# 3_PowerDistribution.net
KiCad netlist of a schematic drawn in Altium Designer
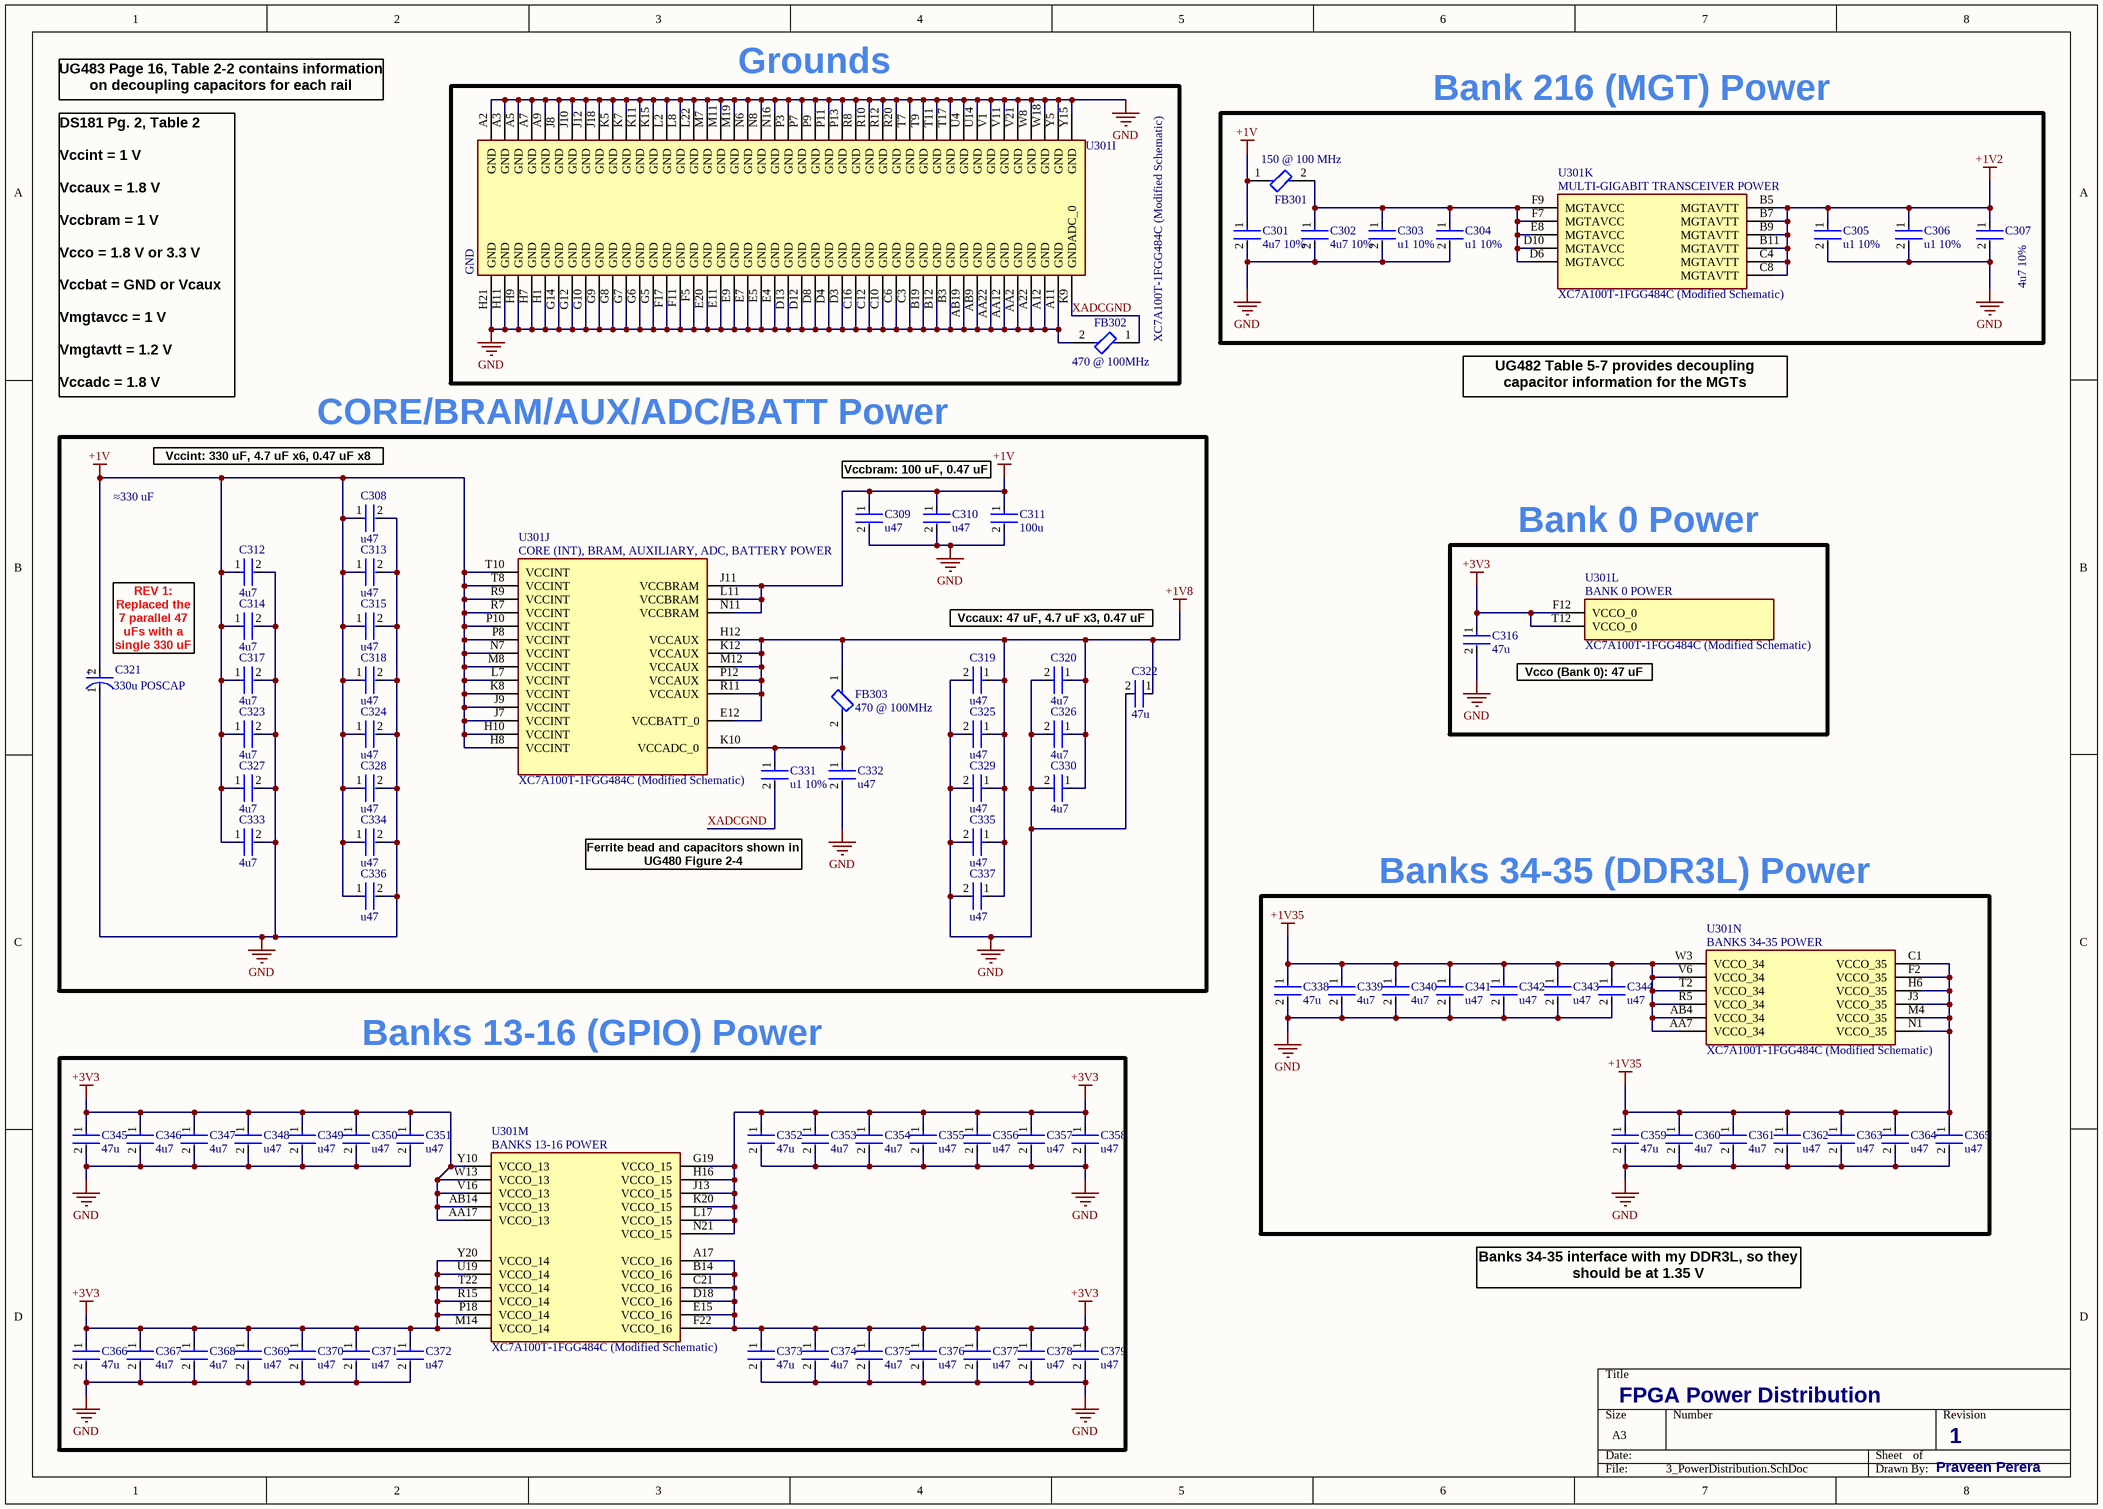
[diagram p0: 3_PowerDistribution.SchDoc]

(export (version "E")
  (design (tool "Eeschema 10.0.6"))
  (components
    (comp (ref "C301")
      (value "4u7 10%")
      (footprint "FP-C1005-050-0_20-0_10-MFG")
      (description "C1005X5R1A475K050BE\r\n\r\nCAP CER 4.7UF 10V X5R 0402")
      (fields (field (name "TOLERANCE") "10%"))
      (libsource (lib "Altium Content Vault") (part "b4654b650e69147ec39a6b967a45e02"))
    )
    (comp (ref "C302")
      (value "4u7 10%")
      (footprint "FP-C1005-050-0_20-0_10-MFG")
      (description "C1005X5R1A475K050BE\r\n\r\nCAP CER 4.7UF 10V X5R 0402")
      (fields (field (name "TOLERANCE") "10%"))
      (libsource (lib "Altium Content Vault") (part "b4654b650e69147ec39a6b967a45e02"))
    )
    (comp (ref "C303")
      (value "u1 10%")
      (footprint "FP-CL891-IPC_C")
      (description "CL05B104KB5NNNC\r\n\r\nCap Ceramic 100nF 50V X7R ±10% SMD 0402 +125°C Paper T/R")
      (libsource (lib "Altium Content Vault") (part "b4654b650e69147ec39a6b967a45e02"))
    )
    (comp (ref "C304")
      (value "u1 10%")
      (footprint "FP-CL891-IPC_C")
      (description "CL05B104KB5NNNC\r\n\r\nCap Ceramic 100nF 50V X7R ±10% SMD 0402 +125°C Paper T/R")
      (libsource (lib "Altium Content Vault") (part "b4654b650e69147ec39a6b967a45e02"))
    )
    (comp (ref "C305")
      (value "u1 10%")
      (footprint "FP-CL891-IPC_C")
      (description "CL05B104KB5NNNC\r\n\r\nCap Ceramic 100nF 50V X7R ±10% SMD 0402 +125°C Paper T/R")
      (libsource (lib "Altium Content Vault") (part "b4654b650e69147ec39a6b967a45e02"))
    )
    (comp (ref "C306")
      (value "u1 10%")
      (footprint "FP-CL891-IPC_C")
      (description "CL05B104KB5NNNC\r\n\r\nCap Ceramic 100nF 50V X7R ±10% SMD 0402 +125°C Paper T/R")
      (libsource (lib "Altium Content Vault") (part "b4654b650e69147ec39a6b967a45e02"))
    )
    (comp (ref "C307")
      (value "4u7 10%")
      (footprint "FP-C1005-050-0_20-0_10-MFG")
      (description "C1005X5R1A475K050BE\r\n\r\nCAP CER 4.7UF 10V X5R 0402")
      (fields (field (name "TOLERANCE") "10%"))
      (libsource (lib "Altium Content Vault") (part "b4654b650e69147ec39a6b967a45e02"))
    )
    (comp (ref "C308")
      (value "u47")
      (footprint "FP-C0603-030-0_03-IPC_A")
      (description "C0603X5R1A474M030BC\r\n\r\nMultilayer Ceramic Capacitors 470nF ±20% 10V X5R SMD 0201")
      (fields (field (name "TOLERANCE") "20%"))
      (libsource (lib "Altium Content Vault") (part "02cd4be3c70576c341d710602a673aa"))
    )
    (comp (ref "C309")
      (value "u47")
      (footprint "FP-C0603-030-0_03-IPC_A")
      (description "C0603X5R1A474M030BC\r\n\r\nMultilayer Ceramic Capacitors 470nF ±20% 10V X5R SMD 0201")
      (fields (field (name "TOLERANCE") "20%"))
      (libsource (lib "Altium Content Vault") (part "02cd4be3c70576c341d710602a673aa"))
    )
    (comp (ref "C310")
      (value "u47")
      (footprint "FP-C0603-030-0_03-IPC_A")
      (description "C0603X5R1A474M030BC\r\n\r\nMultilayer Ceramic Capacitors 470nF ±20% 10V X5R SMD 0201")
      (fields (field (name "TOLERANCE") "20%"))
      (libsource (lib "Altium Content Vault") (part "02cd4be3c70576c341d710602a673aa"))
    )
    (comp (ref "C311")
      (value "100u")
      (footprint "FP-GRM21B-0_2-e0_2_0_7-IPC_A")
      (fields (field (name "TOLERANCE") "20%"))
      (libsource (lib "Altium Content Vault") (part "b4654b650e69147ec39a6b967a45e02"))
    )
    (comp (ref "C312")
      (value "4u7")
      (footprint "FP-CL829-IPC_C")
      (description "CL05A475MO5NUNC\r\n\r\nCap Ceramic 4.7uF 16V X5R ±20% SMD 0402 +85°C Paper T/R")
      (fields (field (name "TOLERANCE") "20%"))
      (libsource (lib "Altium Content Vault") (part "b4654b650e69147ec39a6b967a45e02"))
    )
    (comp (ref "C313")
      (value "u47")
      (footprint "FP-C0603-030-0_03-IPC_A")
      (description "C0603X5R1A474M030BC\r\n\r\nMultilayer Ceramic Capacitors 470nF ±20% 10V X5R SMD 0201")
      (fields (field (name "TOLERANCE") "20%"))
      (libsource (lib "Altium Content Vault") (part "02cd4be3c70576c341d710602a673aa"))
    )
    (comp (ref "C314")
      (value "4u7")
      (footprint "FP-CL829-IPC_C")
      (description "CL05A475MO5NUNC\r\n\r\nCap Ceramic 4.7uF 16V X5R ±20% SMD 0402 +85°C Paper T/R")
      (fields (field (name "TOLERANCE") "20%"))
      (libsource (lib "Altium Content Vault") (part "b4654b650e69147ec39a6b967a45e02"))
    )
    (comp (ref "C315")
      (value "u47")
      (footprint "FP-C0603-030-0_03-IPC_A")
      (description "C0603X5R1A474M030BC\r\n\r\nMultilayer Ceramic Capacitors 470nF ±20% 10V X5R SMD 0201")
      (fields (field (name "TOLERANCE") "20%"))
      (libsource (lib "Altium Content Vault") (part "02cd4be3c70576c341d710602a673aa"))
    )
    (comp (ref "C316")
      (value "47u")
      (footprint "FP-GRM188-0_2-IPC_B")
      (fields (field (name "TOLERANCE") "20%"))
      (libsource (lib "Altium Content Vault") (part "11868f565c42a9108669ba33697ecf6"))
    )
    (comp (ref "C317")
      (value "4u7")
      (footprint "FP-CL829-IPC_C")
      (description "CL05A475MO5NUNC\r\n\r\nCap Ceramic 4.7uF 16V X5R ±20% SMD 0402 +85°C Paper T/R")
      (fields (field (name "TOLERANCE") "20%"))
      (libsource (lib "Altium Content Vault") (part "b4654b650e69147ec39a6b967a45e02"))
    )
    (comp (ref "C318")
      (value "u47")
      (footprint "FP-C0603-030-0_03-IPC_A")
      (description "C0603X5R1A474M030BC\r\n\r\nMultilayer Ceramic Capacitors 470nF ±20% 10V X5R SMD 0201")
      (fields (field (name "TOLERANCE") "20%"))
      (libsource (lib "Altium Content Vault") (part "02cd4be3c70576c341d710602a673aa"))
    )
    (comp (ref "C319")
      (value "u47")
      (footprint "FP-C0603-030-0_03-IPC_A")
      (description "C0603X5R1A474M030BC\r\n\r\nMultilayer Ceramic Capacitors 470nF ±20% 10V X5R SMD 0201")
      (fields (field (name "TOLERANCE") "20%"))
      (libsource (lib "Altium Content Vault") (part "02cd4be3c70576c341d710602a673aa"))
    )
    (comp (ref "C320")
      (value "4u7")
      (footprint "FP-CL829-IPC_C")
      (description "CL05A475MO5NUNC\r\n\r\nCap Ceramic 4.7uF 16V X5R ±20% SMD 0402 +85°C Paper T/R")
      (fields (field (name "TOLERANCE") "20%"))
      (libsource (lib "Altium Content Vault") (part "b4654b650e69147ec39a6b967a45e02"))
    )
    (comp (ref "C321")
      (value "330u POSCAP")
      (footprint "FP-POSCAP-D4-MFG")
      (description "10TCE330M\r\n\r\nCAP TANT POLY 330UF 10V 2917")
      (fields (field (name "TOLERANCE") "20%"))
      (libsource (lib "Altium Content Vault") (part "203bc49f2ac43e59fd269a8c329ed05"))
    )
    (comp (ref "C322")
      (value "47u")
      (footprint "FP-GRM188-0_2-IPC_B")
      (fields (field (name "TOLERANCE") "20%"))
      (libsource (lib "Altium Content Vault") (part "11868f565c42a9108669ba33697ecf6"))
    )
    (comp (ref "C323")
      (value "4u7")
      (footprint "FP-CL829-IPC_C")
      (description "CL05A475MO5NUNC\r\n\r\nCap Ceramic 4.7uF 16V X5R ±20% SMD 0402 +85°C Paper T/R")
      (fields (field (name "TOLERANCE") "20%"))
      (libsource (lib "Altium Content Vault") (part "b4654b650e69147ec39a6b967a45e02"))
    )
    (comp (ref "C324")
      (value "u47")
      (footprint "FP-C0603-030-0_03-IPC_A")
      (description "C0603X5R1A474M030BC\r\n\r\nMultilayer Ceramic Capacitors 470nF ±20% 10V X5R SMD 0201")
      (fields (field (name "TOLERANCE") "20%"))
      (libsource (lib "Altium Content Vault") (part "02cd4be3c70576c341d710602a673aa"))
    )
    (comp (ref "C325")
      (value "u47")
      (footprint "FP-C0603-030-0_03-IPC_A")
      (description "C0603X5R1A474M030BC\r\n\r\nMultilayer Ceramic Capacitors 470nF ±20% 10V X5R SMD 0201")
      (fields (field (name "TOLERANCE") "20%"))
      (libsource (lib "Altium Content Vault") (part "02cd4be3c70576c341d710602a673aa"))
    )
    (comp (ref "C326")
      (value "4u7")
      (footprint "FP-CL829-IPC_C")
      (description "CL05A475MO5NUNC\r\n\r\nCap Ceramic 4.7uF 16V X5R ±20% SMD 0402 +85°C Paper T/R")
      (fields (field (name "TOLERANCE") "20%"))
      (libsource (lib "Altium Content Vault") (part "b4654b650e69147ec39a6b967a45e02"))
    )
    (comp (ref "C327")
      (value "4u7")
      (footprint "FP-CL829-IPC_C")
      (description "CL05A475MO5NUNC\r\n\r\nCap Ceramic 4.7uF 16V X5R ±20% SMD 0402 +85°C Paper T/R")
      (fields (field (name "TOLERANCE") "20%"))
      (libsource (lib "Altium Content Vault") (part "b4654b650e69147ec39a6b967a45e02"))
    )
    (comp (ref "C328")
      (value "u47")
      (footprint "FP-C0603-030-0_03-IPC_A")
      (description "C0603X5R1A474M030BC\r\n\r\nMultilayer Ceramic Capacitors 470nF ±20% 10V X5R SMD 0201")
      (fields (field (name "TOLERANCE") "20%"))
      (libsource (lib "Altium Content Vault") (part "02cd4be3c70576c341d710602a673aa"))
    )
    (comp (ref "C329")
      (value "u47")
      (footprint "FP-C0603-030-0_03-IPC_A")
      (description "C0603X5R1A474M030BC\r\n\r\nMultilayer Ceramic Capacitors 470nF ±20% 10V X5R SMD 0201")
      (fields (field (name "TOLERANCE") "20%"))
      (libsource (lib "Altium Content Vault") (part "02cd4be3c70576c341d710602a673aa"))
    )
    (comp (ref "C330")
      (value "4u7")
      (footprint "FP-CL829-IPC_C")
      (description "CL05A475MO5NUNC\r\n\r\nCap Ceramic 4.7uF 16V X5R ±20% SMD 0402 +85°C Paper T/R")
      (fields (field (name "TOLERANCE") "20%"))
      (libsource (lib "Altium Content Vault") (part "b4654b650e69147ec39a6b967a45e02"))
    )
    (comp (ref "C331")
      (value "u1 10%")
      (footprint "FP-CL891-IPC_C")
      (description "CL05B104KB5NNNC\r\n\r\nCap Ceramic 100nF 50V X7R ±10% SMD 0402 +125°C Paper T/R")
      (libsource (lib "Altium Content Vault") (part "b4654b650e69147ec39a6b967a45e02"))
    )
    (comp (ref "C332")
      (value "u47")
      (footprint "FP-C0603-030-0_03-IPC_A")
      (description "C0603X5R1A474M030BC\r\n\r\nMultilayer Ceramic Capacitors 470nF ±20% 10V X5R SMD 0201")
      (fields (field (name "TOLERANCE") "20%"))
      (libsource (lib "Altium Content Vault") (part "02cd4be3c70576c341d710602a673aa"))
    )
    (comp (ref "C333")
      (value "4u7")
      (footprint "FP-CL829-IPC_C")
      (description "CL05A475MO5NUNC\r\n\r\nCap Ceramic 4.7uF 16V X5R ±20% SMD 0402 +85°C Paper T/R")
      (fields (field (name "TOLERANCE") "20%"))
      (libsource (lib "Altium Content Vault") (part "b4654b650e69147ec39a6b967a45e02"))
    )
    (comp (ref "C334")
      (value "u47")
      (footprint "FP-C0603-030-0_03-IPC_A")
      (description "C0603X5R1A474M030BC\r\n\r\nMultilayer Ceramic Capacitors 470nF ±20% 10V X5R SMD 0201")
      (fields (field (name "TOLERANCE") "20%"))
      (libsource (lib "Altium Content Vault") (part "02cd4be3c70576c341d710602a673aa"))
    )
    (comp (ref "C335")
      (value "u47")
      (footprint "FP-C0603-030-0_03-IPC_A")
      (description "C0603X5R1A474M030BC\r\n\r\nMultilayer Ceramic Capacitors 470nF ±20% 10V X5R SMD 0201")
      (fields (field (name "TOLERANCE") "20%"))
      (libsource (lib "Altium Content Vault") (part "02cd4be3c70576c341d710602a673aa"))
    )
    (comp (ref "C336")
      (value "u47")
      (footprint "FP-C0603-030-0_03-IPC_A")
      (description "C0603X5R1A474M030BC\r\n\r\nMultilayer Ceramic Capacitors 470nF ±20% 10V X5R SMD 0201")
      (fields (field (name "TOLERANCE") "20%"))
      (libsource (lib "Altium Content Vault") (part "02cd4be3c70576c341d710602a673aa"))
    )
    (comp (ref "C337")
      (value "u47")
      (footprint "FP-C0603-030-0_03-IPC_A")
      (description "C0603X5R1A474M030BC\r\n\r\nMultilayer Ceramic Capacitors 470nF ±20% 10V X5R SMD 0201")
      (fields (field (name "TOLERANCE") "20%"))
      (libsource (lib "Altium Content Vault") (part "02cd4be3c70576c341d710602a673aa"))
    )
    (comp (ref "C338")
      (value "47u")
      (footprint "FP-GRM188-0_2-IPC_B")
      (fields (field (name "TOLERANCE") "20%"))
      (libsource (lib "Altium Content Vault") (part "11868f565c42a9108669ba33697ecf6"))
    )
    (comp (ref "C339")
      (value "4u7")
      (footprint "FP-CL829-IPC_C")
      (description "CL05A475MO5NUNC\r\n\r\nCap Ceramic 4.7uF 16V X5R ±20% SMD 0402 +85°C Paper T/R")
      (fields (field (name "TOLERANCE") "20%"))
      (libsource (lib "Altium Content Vault") (part "b4654b650e69147ec39a6b967a45e02"))
    )
    (comp (ref "C340")
      (value "4u7")
      (footprint "FP-CL829-IPC_C")
      (description "CL05A475MO5NUNC\r\n\r\nCap Ceramic 4.7uF 16V X5R ±20% SMD 0402 +85°C Paper T/R")
      (fields (field (name "TOLERANCE") "20%"))
      (libsource (lib "Altium Content Vault") (part "b4654b650e69147ec39a6b967a45e02"))
    )
    (comp (ref "C341")
      (value "u47")
      (footprint "FP-C0603-030-0_03-IPC_A")
      (description "C0603X5R1A474M030BC\r\n\r\nMultilayer Ceramic Capacitors 470nF ±20% 10V X5R SMD 0201")
      (fields (field (name "TOLERANCE") "20%"))
      (libsource (lib "Altium Content Vault") (part "02cd4be3c70576c341d710602a673aa"))
    )
    (comp (ref "C342")
      (value "u47")
      (footprint "FP-C0603-030-0_03-IPC_A")
      (description "C0603X5R1A474M030BC\r\n\r\nMultilayer Ceramic Capacitors 470nF ±20% 10V X5R SMD 0201")
      (fields (field (name "TOLERANCE") "20%"))
      (libsource (lib "Altium Content Vault") (part "02cd4be3c70576c341d710602a673aa"))
    )
    (comp (ref "C343")
      (value "u47")
      (footprint "FP-C0603-030-0_03-IPC_A")
      (description "C0603X5R1A474M030BC\r\n\r\nMultilayer Ceramic Capacitors 470nF ±20% 10V X5R SMD 0201")
      (fields (field (name "TOLERANCE") "20%"))
      (libsource (lib "Altium Content Vault") (part "02cd4be3c70576c341d710602a673aa"))
    )
    (comp (ref "C344")
      (value "u47")
      (footprint "FP-C0603-030-0_03-IPC_A")
      (description "C0603X5R1A474M030BC\r\n\r\nMultilayer Ceramic Capacitors 470nF ±20% 10V X5R SMD 0201")
      (fields (field (name "TOLERANCE") "20%"))
      (libsource (lib "Altium Content Vault") (part "02cd4be3c70576c341d710602a673aa"))
    )
    (comp (ref "C345")
      (value "47u")
      (footprint "FP-GRM188-0_2-IPC_B")
      (fields (field (name "TOLERANCE") "20%"))
      (libsource (lib "Altium Content Vault") (part "11868f565c42a9108669ba33697ecf6"))
    )
    (comp (ref "C346")
      (value "4u7")
      (footprint "FP-CL829-IPC_C")
      (description "CL05A475MO5NUNC\r\n\r\nCap Ceramic 4.7uF 16V X5R ±20% SMD 0402 +85°C Paper T/R")
      (fields (field (name "TOLERANCE") "20%"))
      (libsource (lib "Altium Content Vault") (part "b4654b650e69147ec39a6b967a45e02"))
    )
    (comp (ref "C347")
      (value "4u7")
      (footprint "FP-CL829-IPC_C")
      (description "CL05A475MO5NUNC\r\n\r\nCap Ceramic 4.7uF 16V X5R ±20% SMD 0402 +85°C Paper T/R")
      (fields (field (name "TOLERANCE") "20%"))
      (libsource (lib "Altium Content Vault") (part "b4654b650e69147ec39a6b967a45e02"))
    )
    (comp (ref "C348")
      (value "u47")
      (footprint "FP-C0603-030-0_03-IPC_A")
      (description "C0603X5R1A474M030BC\r\n\r\nMultilayer Ceramic Capacitors 470nF ±20% 10V X5R SMD 0201")
      (fields (field (name "TOLERANCE") "20%"))
      (libsource (lib "Altium Content Vault") (part "02cd4be3c70576c341d710602a673aa"))
    )
    (comp (ref "C349")
      (value "u47")
      (footprint "FP-C0603-030-0_03-IPC_A")
      (description "C0603X5R1A474M030BC\r\n\r\nMultilayer Ceramic Capacitors 470nF ±20% 10V X5R SMD 0201")
      (fields (field (name "TOLERANCE") "20%"))
      (libsource (lib "Altium Content Vault") (part "02cd4be3c70576c341d710602a673aa"))
    )
    (comp (ref "C350")
      (value "u47")
      (footprint "FP-C0603-030-0_03-IPC_A")
      (description "C0603X5R1A474M030BC\r\n\r\nMultilayer Ceramic Capacitors 470nF ±20% 10V X5R SMD 0201")
      (fields (field (name "TOLERANCE") "20%"))
      (libsource (lib "Altium Content Vault") (part "02cd4be3c70576c341d710602a673aa"))
    )
    (comp (ref "C351")
      (value "u47")
      (footprint "FP-C0603-030-0_03-IPC_A")
      (description "C0603X5R1A474M030BC\r\n\r\nMultilayer Ceramic Capacitors 470nF ±20% 10V X5R SMD 0201")
      (fields (field (name "TOLERANCE") "20%"))
      (libsource (lib "Altium Content Vault") (part "02cd4be3c70576c341d710602a673aa"))
    )
    (comp (ref "C352")
      (value "47u")
      (footprint "FP-GRM188-0_2-IPC_B")
      (fields (field (name "TOLERANCE") "20%"))
      (libsource (lib "Altium Content Vault") (part "11868f565c42a9108669ba33697ecf6"))
    )
    (comp (ref "C353")
      (value "4u7")
      (footprint "FP-CL829-IPC_C")
      (description "CL05A475MO5NUNC\r\n\r\nCap Ceramic 4.7uF 16V X5R ±20% SMD 0402 +85°C Paper T/R")
      (fields (field (name "TOLERANCE") "20%"))
      (libsource (lib "Altium Content Vault") (part "b4654b650e69147ec39a6b967a45e02"))
    )
    (comp (ref "C354")
      (value "4u7")
      (footprint "FP-CL829-IPC_C")
      (description "CL05A475MO5NUNC\r\n\r\nCap Ceramic 4.7uF 16V X5R ±20% SMD 0402 +85°C Paper T/R")
      (fields (field (name "TOLERANCE") "20%"))
      (libsource (lib "Altium Content Vault") (part "b4654b650e69147ec39a6b967a45e02"))
    )
    (comp (ref "C355")
      (value "u47")
      (footprint "FP-C0603-030-0_03-IPC_A")
      (description "C0603X5R1A474M030BC\r\n\r\nMultilayer Ceramic Capacitors 470nF ±20% 10V X5R SMD 0201")
      (fields (field (name "TOLERANCE") "20%"))
      (libsource (lib "Altium Content Vault") (part "02cd4be3c70576c341d710602a673aa"))
    )
    (comp (ref "C356")
      (value "u47")
      (footprint "FP-C0603-030-0_03-IPC_A")
      (description "C0603X5R1A474M030BC\r\n\r\nMultilayer Ceramic Capacitors 470nF ±20% 10V X5R SMD 0201")
      (fields (field (name "TOLERANCE") "20%"))
      (libsource (lib "Altium Content Vault") (part "02cd4be3c70576c341d710602a673aa"))
    )
    (comp (ref "C357")
      (value "u47")
      (footprint "FP-C0603-030-0_03-IPC_A")
      (description "C0603X5R1A474M030BC\r\n\r\nMultilayer Ceramic Capacitors 470nF ±20% 10V X5R SMD 0201")
      (fields (field (name "TOLERANCE") "20%"))
      (libsource (lib "Altium Content Vault") (part "02cd4be3c70576c341d710602a673aa"))
    )
    (comp (ref "C358")
      (value "u47")
      (footprint "FP-C0603-030-0_03-IPC_A")
      (description "C0603X5R1A474M030BC\r\n\r\nMultilayer Ceramic Capacitors 470nF ±20% 10V X5R SMD 0201")
      (fields (field (name "TOLERANCE") "20%"))
      (libsource (lib "Altium Content Vault") (part "02cd4be3c70576c341d710602a673aa"))
    )
    (comp (ref "C359")
      (value "47u")
      (footprint "FP-GRM188-0_2-IPC_B")
      (fields (field (name "TOLERANCE") "20%"))
      (libsource (lib "Altium Content Vault") (part "11868f565c42a9108669ba33697ecf6"))
    )
    (comp (ref "C360")
      (value "4u7")
      (footprint "FP-CL829-IPC_C")
      (description "CL05A475MO5NUNC\r\n\r\nCap Ceramic 4.7uF 16V X5R ±20% SMD 0402 +85°C Paper T/R")
      (fields (field (name "TOLERANCE") "20%"))
      (libsource (lib "Altium Content Vault") (part "b4654b650e69147ec39a6b967a45e02"))
    )
    (comp (ref "C361")
      (value "4u7")
      (footprint "FP-CL829-IPC_C")
      (description "CL05A475MO5NUNC\r\n\r\nCap Ceramic 4.7uF 16V X5R ±20% SMD 0402 +85°C Paper T/R")
      (fields (field (name "TOLERANCE") "20%"))
      (libsource (lib "Altium Content Vault") (part "b4654b650e69147ec39a6b967a45e02"))
    )
    (comp (ref "C362")
      (value "u47")
      (footprint "FP-C0603-030-0_03-IPC_A")
      (description "C0603X5R1A474M030BC\r\n\r\nMultilayer Ceramic Capacitors 470nF ±20% 10V X5R SMD 0201")
      (fields (field (name "TOLERANCE") "20%"))
      (libsource (lib "Altium Content Vault") (part "02cd4be3c70576c341d710602a673aa"))
    )
    (comp (ref "C363")
      (value "u47")
      (footprint "FP-C0603-030-0_03-IPC_A")
      (description "C0603X5R1A474M030BC\r\n\r\nMultilayer Ceramic Capacitors 470nF ±20% 10V X5R SMD 0201")
      (fields (field (name "TOLERANCE") "20%"))
      (libsource (lib "Altium Content Vault") (part "02cd4be3c70576c341d710602a673aa"))
    )
    (comp (ref "C364")
      (value "u47")
      (footprint "FP-C0603-030-0_03-IPC_A")
      (description "C0603X5R1A474M030BC\r\n\r\nMultilayer Ceramic Capacitors 470nF ±20% 10V X5R SMD 0201")
      (fields (field (name "TOLERANCE") "20%"))
      (libsource (lib "Altium Content Vault") (part "02cd4be3c70576c341d710602a673aa"))
    )
    (comp (ref "C365")
      (value "u47")
      (footprint "FP-C0603-030-0_03-IPC_A")
      (description "C0603X5R1A474M030BC\r\n\r\nMultilayer Ceramic Capacitors 470nF ±20% 10V X5R SMD 0201")
      (fields (field (name "TOLERANCE") "20%"))
      (libsource (lib "Altium Content Vault") (part "02cd4be3c70576c341d710602a673aa"))
    )
    (comp (ref "C366")
      (value "47u")
      (footprint "FP-GRM188-0_2-IPC_B")
      (fields (field (name "TOLERANCE") "20%"))
      (libsource (lib "Altium Content Vault") (part "11868f565c42a9108669ba33697ecf6"))
    )
    (comp (ref "C367")
      (value "4u7")
      (footprint "FP-CL829-IPC_C")
      (description "CL05A475MO5NUNC\r\n\r\nCap Ceramic 4.7uF 16V X5R ±20% SMD 0402 +85°C Paper T/R")
      (fields (field (name "TOLERANCE") "20%"))
      (libsource (lib "Altium Content Vault") (part "b4654b650e69147ec39a6b967a45e02"))
    )
    (comp (ref "C368")
      (value "4u7")
      (footprint "FP-CL829-IPC_C")
      (description "CL05A475MO5NUNC\r\n\r\nCap Ceramic 4.7uF 16V X5R ±20% SMD 0402 +85°C Paper T/R")
      (fields (field (name "TOLERANCE") "20%"))
      (libsource (lib "Altium Content Vault") (part "b4654b650e69147ec39a6b967a45e02"))
    )
    (comp (ref "C369")
      (value "u47")
      (footprint "FP-C0603-030-0_03-IPC_A")
      (description "C0603X5R1A474M030BC\r\n\r\nMultilayer Ceramic Capacitors 470nF ±20% 10V X5R SMD 0201")
      (fields (field (name "TOLERANCE") "20%"))
      (libsource (lib "Altium Content Vault") (part "02cd4be3c70576c341d710602a673aa"))
    )
    (comp (ref "C370")
      (value "u47")
      (footprint "FP-C0603-030-0_03-IPC_A")
      (description "C0603X5R1A474M030BC\r\n\r\nMultilayer Ceramic Capacitors 470nF ±20% 10V X5R SMD 0201")
      (fields (field (name "TOLERANCE") "20%"))
      (libsource (lib "Altium Content Vault") (part "02cd4be3c70576c341d710602a673aa"))
    )
    (comp (ref "C371")
      (value "u47")
      (footprint "FP-C0603-030-0_03-IPC_A")
      (description "C0603X5R1A474M030BC\r\n\r\nMultilayer Ceramic Capacitors 470nF ±20% 10V X5R SMD 0201")
      (fields (field (name "TOLERANCE") "20%"))
      (libsource (lib "Altium Content Vault") (part "02cd4be3c70576c341d710602a673aa"))
    )
    (comp (ref "C372")
      (value "u47")
      (footprint "FP-C0603-030-0_03-IPC_A")
      (description "C0603X5R1A474M030BC\r\n\r\nMultilayer Ceramic Capacitors 470nF ±20% 10V X5R SMD 0201")
      (fields (field (name "TOLERANCE") "20%"))
      (libsource (lib "Altium Content Vault") (part "02cd4be3c70576c341d710602a673aa"))
    )
    (comp (ref "C373")
      (value "47u")
      (footprint "FP-GRM188-0_2-IPC_B")
      (fields (field (name "TOLERANCE") "20%"))
      (libsource (lib "Altium Content Vault") (part "11868f565c42a9108669ba33697ecf6"))
    )
    (comp (ref "C374")
      (value "4u7")
      (footprint "FP-CL829-IPC_C")
      (description "CL05A475MO5NUNC\r\n\r\nCap Ceramic 4.7uF 16V X5R ±20% SMD 0402 +85°C Paper T/R")
      (fields (field (name "TOLERANCE") "20%"))
      (libsource (lib "Altium Content Vault") (part "b4654b650e69147ec39a6b967a45e02"))
    )
    (comp (ref "C375")
      (value "4u7")
      (footprint "FP-CL829-IPC_C")
      (description "CL05A475MO5NUNC\r\n\r\nCap Ceramic 4.7uF 16V X5R ±20% SMD 0402 +85°C Paper T/R")
      (fields (field (name "TOLERANCE") "20%"))
      (libsource (lib "Altium Content Vault") (part "b4654b650e69147ec39a6b967a45e02"))
    )
    (comp (ref "C376")
      (value "u47")
      (footprint "FP-C0603-030-0_03-IPC_A")
      (description "C0603X5R1A474M030BC\r\n\r\nMultilayer Ceramic Capacitors 470nF ±20% 10V X5R SMD 0201")
      (fields (field (name "TOLERANCE") "20%"))
      (libsource (lib "Altium Content Vault") (part "02cd4be3c70576c341d710602a673aa"))
    )
    (comp (ref "C377")
      (value "u47")
      (footprint "FP-C0603-030-0_03-IPC_A")
      (description "C0603X5R1A474M030BC\r\n\r\nMultilayer Ceramic Capacitors 470nF ±20% 10V X5R SMD 0201")
      (fields (field (name "TOLERANCE") "20%"))
      (libsource (lib "Altium Content Vault") (part "02cd4be3c70576c341d710602a673aa"))
    )
    (comp (ref "C378")
      (value "u47")
      (footprint "FP-C0603-030-0_03-IPC_A")
      (description "C0603X5R1A474M030BC\r\n\r\nMultilayer Ceramic Capacitors 470nF ±20% 10V X5R SMD 0201")
      (fields (field (name "TOLERANCE") "20%"))
      (libsource (lib "Altium Content Vault") (part "02cd4be3c70576c341d710602a673aa"))
    )
    (comp (ref "C379")
      (value "u47")
      (footprint "FP-C0603-030-0_03-IPC_A")
      (description "C0603X5R1A474M030BC\r\n\r\nMultilayer Ceramic Capacitors 470nF ±20% 10V X5R SMD 0201")
      (fields (field (name "TOLERANCE") "20%"))
      (libsource (lib "Altium Content Vault") (part "02cd4be3c70576c341d710602a673aa"))
    )
    (comp (ref "FB301")
      (value "150 @ 100 MHz")
      (footprint "FP-MPZ1005-IPC_B")
      (description "MPZ1005A151ETD25\r\n\r\nPower line Ferrite Bead 150Ω @ 100MHz 0.8A DCR 0.18Ω AEC-Q200 SMD 0402")
      (libsource (lib "Altium Content Vault") (part "5f30dd21d616792df468990f7003faa"))
    )
    (comp (ref "FB302")
      (value "470 @ 100MHz")
      (footprint "FP-BLM41-0_2-a1_2-IPC_B")
      (description "BLM41PG471SN1L\r\n\r\nFerrite Bead, 1806, 470Ω @ 100MHz, 25%, 0.05Ω, 2A")
      (fields (field (name "TOLERANCE") "25%"))
      (libsource (lib "Altium Content Vault") (part "5f30dd21d616792df468990f7003faa"))
    )
    (comp (ref "FB303")
      (value "470 @ 100MHz")
      (footprint "FP-BLM41-0_2-a1_2-IPC_B")
      (description "BLM41PG471SN1L\r\n\r\nFerrite Bead, 1806, 470Ω @ 100MHz, 25%, 0.05Ω, 2A")
      (fields (field (name "TOLERANCE") "25%"))
      (libsource (lib "Altium Content Vault") (part "5f30dd21d616792df468990f7003faa"))
    )
    (comp (ref "U301")
      (value "XC7A100T-1FGG484C (Modified Schematic)")
      (footprint "BGA484C100P22X22_2300X2300X260N")
      (description "Artix-7 Field Programmable Gate Array (FPGA) IC 285 4976640 101440 484-BBGA")
      (fields (field (name "MP") "XC7A100T-1FGG484C") (field (name "MF") "Xilinx Inc."))
      (libsource (lib "XC7A100T-1FGG484C - Modified") (part "XC7A100T-1FGG484C"))
    )
  )
  (nets
    (net (code "1") (name "+1V") (class "Default")
      (node (ref "C301") (pin "1") (pinfunction "1_1") (pintype "passive"))
      (node (ref "C308") (pin "1") (pinfunction "1_1") (pintype "passive"))
      (node (ref "C309") (pin "1") (pinfunction "1_1") (pintype "passive"))
      (node (ref "C310") (pin "1") (pinfunction "1_1") (pintype "passive"))
      (node (ref "C311") (pin "1") (pinfunction "1_1") (pintype "passive"))
      (node (ref "C312") (pin "1") (pinfunction "1_1") (pintype "passive"))
      (node (ref "C313") (pin "1") (pinfunction "1_1") (pintype "passive"))
      (node (ref "C314") (pin "1") (pinfunction "1_1") (pintype "passive"))
      (node (ref "C315") (pin "1") (pinfunction "1_1") (pintype "passive"))
      (node (ref "C317") (pin "1") (pinfunction "1_1") (pintype "passive"))
      (node (ref "C318") (pin "1") (pinfunction "1_1") (pintype "passive"))
      (node (ref "C321") (pin "2") (pinfunction "A_2") (pintype "passive"))
      (node (ref "C323") (pin "1") (pinfunction "1_1") (pintype "passive"))
      (node (ref "C324") (pin "1") (pinfunction "1_1") (pintype "passive"))
      (node (ref "C327") (pin "1") (pinfunction "1_1") (pintype "passive"))
      (node (ref "C328") (pin "1") (pinfunction "1_1") (pintype "passive"))
      (node (ref "C333") (pin "1") (pinfunction "1_1") (pintype "passive"))
      (node (ref "C334") (pin "1") (pinfunction "1_1") (pintype "passive"))
      (node (ref "C336") (pin "1") (pinfunction "1_1") (pintype "passive"))
      (node (ref "FB301") (pin "1") (pinfunction "1_1") (pintype "passive"))
      (node (ref "U301") (pin "H10") (pinfunction "VCCINT_H10") (pintype "power_in"))
      (node (ref "U301") (pin "H8") (pinfunction "VCCINT_H8") (pintype "power_in"))
      (node (ref "U301") (pin "J11") (pinfunction "VCCBRAM_J11") (pintype "power_in"))
      (node (ref "U301") (pin "J7") (pinfunction "VCCINT_J7") (pintype "power_in"))
      (node (ref "U301") (pin "J9") (pinfunction "VCCINT_J9") (pintype "power_in"))
      (node (ref "U301") (pin "K8") (pinfunction "VCCINT_K8") (pintype "power_in"))
      (node (ref "U301") (pin "L11") (pinfunction "VCCBRAM_L11") (pintype "power_in"))
      (node (ref "U301") (pin "L7") (pinfunction "VCCINT_L7") (pintype "power_in"))
      (node (ref "U301") (pin "M8") (pinfunction "VCCINT_M8") (pintype "power_in"))
      (node (ref "U301") (pin "N11") (pinfunction "VCCBRAM_N11") (pintype "power_in"))
      (node (ref "U301") (pin "N7") (pinfunction "VCCINT_N7") (pintype "power_in"))
      (node (ref "U301") (pin "P10") (pinfunction "VCCINT_P10") (pintype "power_in"))
      (node (ref "U301") (pin "P8") (pinfunction "VCCINT_P8") (pintype "power_in"))
      (node (ref "U301") (pin "R7") (pinfunction "VCCINT_R7") (pintype "power_in"))
      (node (ref "U301") (pin "R9") (pinfunction "VCCINT_R9") (pintype "power_in"))
      (node (ref "U301") (pin "T10") (pinfunction "VCCINT_T10") (pintype "power_in"))
      (node (ref "U301") (pin "T8") (pinfunction "VCCINT_T8") (pintype "power_in"))
    )
    (net (code "2") (name "+1V2") (class "Default")
      (node (ref "C305") (pin "1") (pinfunction "1_1") (pintype "passive"))
      (node (ref "C306") (pin "1") (pinfunction "1_1") (pintype "passive"))
      (node (ref "C307") (pin "1") (pinfunction "1_1") (pintype "passive"))
      (node (ref "U301") (pin "B11") (pinfunction "MGTAVTT_B11") (pintype "power_in"))
      (node (ref "U301") (pin "B5") (pinfunction "MGTAVTT_B5") (pintype "power_in"))
      (node (ref "U301") (pin "B7") (pinfunction "MGTAVTT_B7") (pintype "power_in"))
      (node (ref "U301") (pin "B9") (pinfunction "MGTAVTT_B9") (pintype "power_in"))
      (node (ref "U301") (pin "C4") (pinfunction "MGTAVTT_C4") (pintype "power_in"))
      (node (ref "U301") (pin "C8") (pinfunction "MGTAVTT_C8") (pintype "power_in"))
    )
    (net (code "3") (name "+1V8") (class "Default")
      (node (ref "C319") (pin "1") (pinfunction "1_1") (pintype "passive"))
      (node (ref "C320") (pin "1") (pinfunction "1_1") (pintype "passive"))
      (node (ref "C322") (pin "1") (pinfunction "1_1") (pintype "passive"))
      (node (ref "C325") (pin "1") (pinfunction "1_1") (pintype "passive"))
      (node (ref "C326") (pin "1") (pinfunction "1_1") (pintype "passive"))
      (node (ref "C329") (pin "1") (pinfunction "1_1") (pintype "passive"))
      (node (ref "C330") (pin "1") (pinfunction "1_1") (pintype "passive"))
      (node (ref "C335") (pin "1") (pinfunction "1_1") (pintype "passive"))
      (node (ref "C337") (pin "1") (pinfunction "1_1") (pintype "passive"))
      (node (ref "FB303") (pin "1") (pinfunction "1_1") (pintype "passive"))
      (node (ref "U301") (pin "E12") (pinfunction "VCCBATT_0_E12") (pintype "power_in"))
      (node (ref "U301") (pin "H12") (pinfunction "VCCAUX_H12") (pintype "power_in"))
      (node (ref "U301") (pin "K12") (pinfunction "VCCAUX_K12") (pintype "power_in"))
      (node (ref "U301") (pin "M12") (pinfunction "VCCAUX_M12") (pintype "power_in"))
      (node (ref "U301") (pin "P12") (pinfunction "VCCAUX_P12") (pintype "power_in"))
      (node (ref "U301") (pin "R11") (pinfunction "VCCAUX_R11") (pintype "power_in"))
    )
    (net (code "4") (name "+1V35") (class "Default")
      (node (ref "C338") (pin "1") (pinfunction "1_1") (pintype "passive"))
      (node (ref "C339") (pin "1") (pinfunction "1_1") (pintype "passive"))
      (node (ref "C340") (pin "1") (pinfunction "1_1") (pintype "passive"))
      (node (ref "C341") (pin "1") (pinfunction "1_1") (pintype "passive"))
      (node (ref "C342") (pin "1") (pinfunction "1_1") (pintype "passive"))
      (node (ref "C343") (pin "1") (pinfunction "1_1") (pintype "passive"))
      (node (ref "C344") (pin "1") (pinfunction "1_1") (pintype "passive"))
      (node (ref "C359") (pin "1") (pinfunction "1_1") (pintype "passive"))
      (node (ref "C360") (pin "1") (pinfunction "1_1") (pintype "passive"))
      (node (ref "C361") (pin "1") (pinfunction "1_1") (pintype "passive"))
      (node (ref "C362") (pin "1") (pinfunction "1_1") (pintype "passive"))
      (node (ref "C363") (pin "1") (pinfunction "1_1") (pintype "passive"))
      (node (ref "C364") (pin "1") (pinfunction "1_1") (pintype "passive"))
      (node (ref "C365") (pin "1") (pinfunction "1_1") (pintype "passive"))
      (node (ref "U301") (pin "AA7") (pinfunction "VCCO_34_AA7") (pintype "power_in"))
      (node (ref "U301") (pin "AB4") (pinfunction "VCCO_34_AB4") (pintype "power_in"))
      (node (ref "U301") (pin "C1") (pinfunction "VCCO_35_C1") (pintype "power_in"))
      (node (ref "U301") (pin "F2") (pinfunction "VCCO_35_F2") (pintype "power_in"))
      (node (ref "U301") (pin "H6") (pinfunction "VCCO_35_H6") (pintype "power_in"))
      (node (ref "U301") (pin "J3") (pinfunction "VCCO_35_J3") (pintype "power_in"))
      (node (ref "U301") (pin "M4") (pinfunction "VCCO_35_M4") (pintype "power_in"))
      (node (ref "U301") (pin "N1") (pinfunction "VCCO_35_N1") (pintype "power_in"))
      (node (ref "U301") (pin "R5") (pinfunction "VCCO_34_R5") (pintype "power_in"))
      (node (ref "U301") (pin "T2") (pinfunction "VCCO_34_T2") (pintype "power_in"))
      (node (ref "U301") (pin "V6") (pinfunction "VCCO_34_V6") (pintype "power_in"))
      (node (ref "U301") (pin "W3") (pinfunction "VCCO_34_W3") (pintype "power_in"))
    )
    (net (code "5") (name "+3V3") (class "Default")
      (node (ref "C316") (pin "1") (pinfunction "1_1") (pintype "passive"))
      (node (ref "C345") (pin "1") (pinfunction "1_1") (pintype "passive"))
      (node (ref "C346") (pin "1") (pinfunction "1_1") (pintype "passive"))
      (node (ref "C347") (pin "1") (pinfunction "1_1") (pintype "passive"))
      (node (ref "C348") (pin "1") (pinfunction "1_1") (pintype "passive"))
      (node (ref "C349") (pin "1") (pinfunction "1_1") (pintype "passive"))
      (node (ref "C350") (pin "1") (pinfunction "1_1") (pintype "passive"))
      (node (ref "C351") (pin "1") (pinfunction "1_1") (pintype "passive"))
      (node (ref "C352") (pin "1") (pinfunction "1_1") (pintype "passive"))
      (node (ref "C353") (pin "1") (pinfunction "1_1") (pintype "passive"))
      (node (ref "C354") (pin "1") (pinfunction "1_1") (pintype "passive"))
      (node (ref "C355") (pin "1") (pinfunction "1_1") (pintype "passive"))
      (node (ref "C356") (pin "1") (pinfunction "1_1") (pintype "passive"))
      (node (ref "C357") (pin "1") (pinfunction "1_1") (pintype "passive"))
      (node (ref "C358") (pin "1") (pinfunction "1_1") (pintype "passive"))
      (node (ref "C366") (pin "1") (pinfunction "1_1") (pintype "passive"))
      (node (ref "C367") (pin "1") (pinfunction "1_1") (pintype "passive"))
      (node (ref "C368") (pin "1") (pinfunction "1_1") (pintype "passive"))
      (node (ref "C369") (pin "1") (pinfunction "1_1") (pintype "passive"))
      (node (ref "C370") (pin "1") (pinfunction "1_1") (pintype "passive"))
      (node (ref "C371") (pin "1") (pinfunction "1_1") (pintype "passive"))
      (node (ref "C372") (pin "1") (pinfunction "1_1") (pintype "passive"))
      (node (ref "C373") (pin "1") (pinfunction "1_1") (pintype "passive"))
      (node (ref "C374") (pin "1") (pinfunction "1_1") (pintype "passive"))
      (node (ref "C375") (pin "1") (pinfunction "1_1") (pintype "passive"))
      (node (ref "C376") (pin "1") (pinfunction "1_1") (pintype "passive"))
      (node (ref "C377") (pin "1") (pinfunction "1_1") (pintype "passive"))
      (node (ref "C378") (pin "1") (pinfunction "1_1") (pintype "passive"))
      (node (ref "C379") (pin "1") (pinfunction "1_1") (pintype "passive"))
      (node (ref "U301") (pin "A17") (pinfunction "VCCO_16_A17") (pintype "power_in"))
      (node (ref "U301") (pin "AA17") (pinfunction "VCCO_13_AA17") (pintype "power_in"))
      (node (ref "U301") (pin "AB14") (pinfunction "VCCO_13_AB14") (pintype "power_in"))
      (node (ref "U301") (pin "B14") (pinfunction "VCCO_16_B14") (pintype "power_in"))
      (node (ref "U301") (pin "C21") (pinfunction "VCCO_16_C21") (pintype "power_in"))
      (node (ref "U301") (pin "D18") (pinfunction "VCCO_16_D18") (pintype "power_in"))
      (node (ref "U301") (pin "E15") (pinfunction "VCCO_16_E15") (pintype "power_in"))
      (node (ref "U301") (pin "F12") (pinfunction "VCCO_0_F12") (pintype "power_in"))
      (node (ref "U301") (pin "F22") (pinfunction "VCCO_16_F22") (pintype "power_in"))
      (node (ref "U301") (pin "G19") (pinfunction "VCCO_15_G19") (pintype "power_in"))
      (node (ref "U301") (pin "H16") (pinfunction "VCCO_15_H16") (pintype "power_in"))
      (node (ref "U301") (pin "J13") (pinfunction "VCCO_15_J13") (pintype "power_in"))
      (node (ref "U301") (pin "K20") (pinfunction "VCCO_15_K20") (pintype "power_in"))
      (node (ref "U301") (pin "L17") (pinfunction "VCCO_15_L17") (pintype "power_in"))
      (node (ref "U301") (pin "M14") (pinfunction "VCCO_14_M14") (pintype "power_in"))
      (node (ref "U301") (pin "N21") (pinfunction "VCCO_15_N21") (pintype "power_in"))
      (node (ref "U301") (pin "P18") (pinfunction "VCCO_14_P18") (pintype "power_in"))
      (node (ref "U301") (pin "R15") (pinfunction "VCCO_14_R15") (pintype "power_in"))
      (node (ref "U301") (pin "T12") (pinfunction "VCCO_0_T12") (pintype "power_in"))
      (node (ref "U301") (pin "T22") (pinfunction "VCCO_14_T22") (pintype "power_in"))
      (node (ref "U301") (pin "U19") (pinfunction "VCCO_14_U19") (pintype "power_in"))
      (node (ref "U301") (pin "V16") (pinfunction "VCCO_13_V16") (pintype "power_in"))
      (node (ref "U301") (pin "W13") (pinfunction "VCCO_13_W13") (pintype "power_in"))
      (node (ref "U301") (pin "Y10") (pinfunction "VCCO_13_Y10") (pintype "power_in"))
      (node (ref "U301") (pin "Y20") (pinfunction "VCCO_14_Y20") (pintype "power_in"))
    )
    (net (code "6") (name "/XADCGND") (class "Default")
      (node (ref "C331") (pin "2") (pinfunction "2_2") (pintype "passive"))
      (node (ref "FB302") (pin "1") (pinfunction "1_1") (pintype "passive"))
      (node (ref "U301") (pin "K9") (pinfunction "GNDADC_0_K9") (pintype "power_in"))
    )
    (net (code "7") (name "GND") (class "Default")
      (node (ref "C301") (pin "2") (pinfunction "2_2") (pintype "passive"))
      (node (ref "C302") (pin "2") (pinfunction "2_2") (pintype "passive"))
      (node (ref "C303") (pin "2") (pinfunction "2_2") (pintype "passive"))
      (node (ref "C304") (pin "2") (pinfunction "2_2") (pintype "passive"))
      (node (ref "C305") (pin "2") (pinfunction "2_2") (pintype "passive"))
      (node (ref "C306") (pin "2") (pinfunction "2_2") (pintype "passive"))
      (node (ref "C307") (pin "2") (pinfunction "2_2") (pintype "passive"))
      (node (ref "C308") (pin "2") (pinfunction "2_2") (pintype "passive"))
      (node (ref "C309") (pin "2") (pinfunction "2_2") (pintype "passive"))
      (node (ref "C310") (pin "2") (pinfunction "2_2") (pintype "passive"))
      (node (ref "C311") (pin "2") (pinfunction "2_2") (pintype "passive"))
      (node (ref "C312") (pin "2") (pinfunction "2_2") (pintype "passive"))
      (node (ref "C313") (pin "2") (pinfunction "2_2") (pintype "passive"))
      (node (ref "C314") (pin "2") (pinfunction "2_2") (pintype "passive"))
      (node (ref "C315") (pin "2") (pinfunction "2_2") (pintype "passive"))
      (node (ref "C316") (pin "2") (pinfunction "2_2") (pintype "passive"))
      (node (ref "C317") (pin "2") (pinfunction "2_2") (pintype "passive"))
      (node (ref "C318") (pin "2") (pinfunction "2_2") (pintype "passive"))
      (node (ref "C319") (pin "2") (pinfunction "2_2") (pintype "passive"))
      (node (ref "C320") (pin "2") (pinfunction "2_2") (pintype "passive"))
      (node (ref "C321") (pin "1") (pinfunction "C_1") (pintype "passive"))
      (node (ref "C322") (pin "2") (pinfunction "2_2") (pintype "passive"))
      (node (ref "C323") (pin "2") (pinfunction "2_2") (pintype "passive"))
      (node (ref "C324") (pin "2") (pinfunction "2_2") (pintype "passive"))
      (node (ref "C325") (pin "2") (pinfunction "2_2") (pintype "passive"))
      (node (ref "C326") (pin "2") (pinfunction "2_2") (pintype "passive"))
      (node (ref "C327") (pin "2") (pinfunction "2_2") (pintype "passive"))
      (node (ref "C328") (pin "2") (pinfunction "2_2") (pintype "passive"))
      (node (ref "C329") (pin "2") (pinfunction "2_2") (pintype "passive"))
      (node (ref "C330") (pin "2") (pinfunction "2_2") (pintype "passive"))
      (node (ref "C332") (pin "2") (pinfunction "2_2") (pintype "passive"))
      (node (ref "C333") (pin "2") (pinfunction "2_2") (pintype "passive"))
      (node (ref "C334") (pin "2") (pinfunction "2_2") (pintype "passive"))
      (node (ref "C335") (pin "2") (pinfunction "2_2") (pintype "passive"))
      (node (ref "C336") (pin "2") (pinfunction "2_2") (pintype "passive"))
      (node (ref "C337") (pin "2") (pinfunction "2_2") (pintype "passive"))
      (node (ref "C338") (pin "2") (pinfunction "2_2") (pintype "passive"))
      (node (ref "C339") (pin "2") (pinfunction "2_2") (pintype "passive"))
      (node (ref "C340") (pin "2") (pinfunction "2_2") (pintype "passive"))
      (node (ref "C341") (pin "2") (pinfunction "2_2") (pintype "passive"))
      (node (ref "C342") (pin "2") (pinfunction "2_2") (pintype "passive"))
      (node (ref "C343") (pin "2") (pinfunction "2_2") (pintype "passive"))
      (node (ref "C344") (pin "2") (pinfunction "2_2") (pintype "passive"))
      (node (ref "C345") (pin "2") (pinfunction "2_2") (pintype "passive"))
      (node (ref "C346") (pin "2") (pinfunction "2_2") (pintype "passive"))
      (node (ref "C347") (pin "2") (pinfunction "2_2") (pintype "passive"))
      (node (ref "C348") (pin "2") (pinfunction "2_2") (pintype "passive"))
      (node (ref "C349") (pin "2") (pinfunction "2_2") (pintype "passive"))
      (node (ref "C350") (pin "2") (pinfunction "2_2") (pintype "passive"))
      (node (ref "C351") (pin "2") (pinfunction "2_2") (pintype "passive"))
      (node (ref "C352") (pin "2") (pinfunction "2_2") (pintype "passive"))
      (node (ref "C353") (pin "2") (pinfunction "2_2") (pintype "passive"))
      (node (ref "C354") (pin "2") (pinfunction "2_2") (pintype "passive"))
      (node (ref "C355") (pin "2") (pinfunction "2_2") (pintype "passive"))
      (node (ref "C356") (pin "2") (pinfunction "2_2") (pintype "passive"))
      (node (ref "C357") (pin "2") (pinfunction "2_2") (pintype "passive"))
      (node (ref "C358") (pin "2") (pinfunction "2_2") (pintype "passive"))
      (node (ref "C359") (pin "2") (pinfunction "2_2") (pintype "passive"))
      (node (ref "C360") (pin "2") (pinfunction "2_2") (pintype "passive"))
      (node (ref "C361") (pin "2") (pinfunction "2_2") (pintype "passive"))
      (node (ref "C362") (pin "2") (pinfunction "2_2") (pintype "passive"))
      (node (ref "C363") (pin "2") (pinfunction "2_2") (pintype "passive"))
      (node (ref "C364") (pin "2") (pinfunction "2_2") (pintype "passive"))
      (node (ref "C365") (pin "2") (pinfunction "2_2") (pintype "passive"))
      (node (ref "C366") (pin "2") (pinfunction "2_2") (pintype "passive"))
      (node (ref "C367") (pin "2") (pinfunction "2_2") (pintype "passive"))
      (node (ref "C368") (pin "2") (pinfunction "2_2") (pintype "passive"))
      (node (ref "C369") (pin "2") (pinfunction "2_2") (pintype "passive"))
      (node (ref "C370") (pin "2") (pinfunction "2_2") (pintype "passive"))
      (node (ref "C371") (pin "2") (pinfunction "2_2") (pintype "passive"))
      (node (ref "C372") (pin "2") (pinfunction "2_2") (pintype "passive"))
      (node (ref "C373") (pin "2") (pinfunction "2_2") (pintype "passive"))
      (node (ref "C374") (pin "2") (pinfunction "2_2") (pintype "passive"))
      (node (ref "C375") (pin "2") (pinfunction "2_2") (pintype "passive"))
      (node (ref "C376") (pin "2") (pinfunction "2_2") (pintype "passive"))
      (node (ref "C377") (pin "2") (pinfunction "2_2") (pintype "passive"))
      (node (ref "C378") (pin "2") (pinfunction "2_2") (pintype "passive"))
      (node (ref "C379") (pin "2") (pinfunction "2_2") (pintype "passive"))
      (node (ref "FB302") (pin "2") (pinfunction "2_2") (pintype "passive"))
      (node (ref "U301") (pin "A11") (pinfunction "GND_A11") (pintype "power_in"))
      (node (ref "U301") (pin "A12") (pinfunction "GND_A12") (pintype "power_in"))
      (node (ref "U301") (pin "A2") (pinfunction "GND_A2") (pintype "power_in"))
      (node (ref "U301") (pin "A22") (pinfunction "GND_A22") (pintype "power_in"))
      (node (ref "U301") (pin "A3") (pinfunction "GND_A3") (pintype "power_in"))
      (node (ref "U301") (pin "A5") (pinfunction "GND_A5") (pintype "power_in"))
      (node (ref "U301") (pin "A7") (pinfunction "GND_A7") (pintype "power_in"))
      (node (ref "U301") (pin "A9") (pinfunction "GND_A9") (pintype "power_in"))
      (node (ref "U301") (pin "AA12") (pinfunction "GND_AA12") (pintype "power_in"))
      (node (ref "U301") (pin "AA2") (pinfunction "GND_AA2") (pintype "power_in"))
      (node (ref "U301") (pin "AA22") (pinfunction "GND_AA22") (pintype "power_in"))
      (node (ref "U301") (pin "AB19") (pinfunction "GND_AB19") (pintype "power_in"))
      (node (ref "U301") (pin "AB9") (pinfunction "GND_AB9") (pintype "power_in"))
      (node (ref "U301") (pin "B12") (pinfunction "GND_B12") (pintype "power_in"))
      (node (ref "U301") (pin "B19") (pinfunction "GND_B19") (pintype "power_in"))
      (node (ref "U301") (pin "B3") (pinfunction "GND_B3") (pintype "power_in"))
      (node (ref "U301") (pin "C10") (pinfunction "GND_C10") (pintype "power_in"))
      (node (ref "U301") (pin "C12") (pinfunction "GND_C12") (pintype "power_in"))
      (node (ref "U301") (pin "C16") (pinfunction "GND_C16") (pintype "power_in"))
      (node (ref "U301") (pin "C3") (pinfunction "GND_C3") (pintype "power_in"))
      (node (ref "U301") (pin "C6") (pinfunction "GND_C6") (pintype "power_in"))
      (node (ref "U301") (pin "D12") (pinfunction "GND_D12") (pintype "power_in"))
      (node (ref "U301") (pin "D13") (pinfunction "GND_D13") (pintype "power_in"))
      (node (ref "U301") (pin "D3") (pinfunction "GND_D3") (pintype "power_in"))
      (node (ref "U301") (pin "D4") (pinfunction "GND_D4") (pintype "power_in"))
      (node (ref "U301") (pin "D8") (pinfunction "GND_D8") (pintype "power_in"))
      (node (ref "U301") (pin "E11") (pinfunction "GND_E11") (pintype "power_in"))
      (node (ref "U301") (pin "E20") (pinfunction "GND_E20") (pintype "power_in"))
      (node (ref "U301") (pin "E4") (pinfunction "GND_E4") (pintype "power_in"))
      (node (ref "U301") (pin "E5") (pinfunction "GND_E5") (pintype "power_in"))
      (node (ref "U301") (pin "E7") (pinfunction "GND_E7") (pintype "power_in"))
      (node (ref "U301") (pin "E9") (pinfunction "GND_E9") (pintype "power_in"))
      (node (ref "U301") (pin "F11") (pinfunction "GND_F11") (pintype "power_in"))
      (node (ref "U301") (pin "F17") (pinfunction "GND_F17") (pintype "power_in"))
      (node (ref "U301") (pin "F5") (pinfunction "GND_F5") (pintype "power_in"))
      (node (ref "U301") (pin "G10") (pinfunction "GND_G10") (pintype "power_in"))
      (node (ref "U301") (pin "G12") (pinfunction "GND_G12") (pintype "power_in"))
      (node (ref "U301") (pin "G14") (pinfunction "GND_G14") (pintype "power_in"))
      (node (ref "U301") (pin "G5") (pinfunction "GND_G5") (pintype "power_in"))
      (node (ref "U301") (pin "G6") (pinfunction "GND_G6") (pintype "power_in"))
      (node (ref "U301") (pin "G7") (pinfunction "GND_G7") (pintype "power_in"))
      (node (ref "U301") (pin "G8") (pinfunction "GND_G8") (pintype "power_in"))
      (node (ref "U301") (pin "G9") (pinfunction "GND_G9") (pintype "power_in"))
      (node (ref "U301") (pin "H1") (pinfunction "GND_H1") (pintype "power_in"))
      (node (ref "U301") (pin "H11") (pinfunction "GND_H11") (pintype "power_in"))
      (node (ref "U301") (pin "H21") (pinfunction "GND_H21") (pintype "power_in"))
      (node (ref "U301") (pin "H7") (pinfunction "GND_H7") (pintype "power_in"))
      (node (ref "U301") (pin "H9") (pinfunction "GND_H9") (pintype "power_in"))
      (node (ref "U301") (pin "J10") (pinfunction "GND_J10") (pintype "power_in"))
      (node (ref "U301") (pin "J12") (pinfunction "GND_J12") (pintype "power_in"))
      (node (ref "U301") (pin "J18") (pinfunction "GND_J18") (pintype "power_in"))
      (node (ref "U301") (pin "J8") (pinfunction "GND_J8") (pintype "power_in"))
      (node (ref "U301") (pin "K11") (pinfunction "GND_K11") (pintype "power_in"))
      (node (ref "U301") (pin "K15") (pinfunction "GND_K15") (pintype "power_in"))
      (node (ref "U301") (pin "K5") (pinfunction "GND_K5") (pintype "power_in"))
      (node (ref "U301") (pin "K7") (pinfunction "GND_K7") (pintype "power_in"))
      (node (ref "U301") (pin "L2") (pinfunction "GND_L2") (pintype "power_in"))
      (node (ref "U301") (pin "L22") (pinfunction "GND_L22") (pintype "power_in"))
      (node (ref "U301") (pin "L8") (pinfunction "GND_L8") (pintype "power_in"))
      (node (ref "U301") (pin "M11") (pinfunction "GND_M11") (pintype "power_in"))
      (node (ref "U301") (pin "M19") (pinfunction "GND_M19") (pintype "power_in"))
      (node (ref "U301") (pin "M7") (pinfunction "GND_M7") (pintype "power_in"))
      (node (ref "U301") (pin "N16") (pinfunction "GND_N16") (pintype "power_in"))
      (node (ref "U301") (pin "N6") (pinfunction "GND_N6") (pintype "power_in"))
      (node (ref "U301") (pin "N8") (pinfunction "GND_N8") (pintype "power_in"))
      (node (ref "U301") (pin "P11") (pinfunction "GND_P11") (pintype "power_in"))
      (node (ref "U301") (pin "P13") (pinfunction "GND_P13") (pintype "power_in"))
      (node (ref "U301") (pin "P3") (pinfunction "GND_P3") (pintype "power_in"))
      (node (ref "U301") (pin "P7") (pinfunction "GND_P7") (pintype "power_in"))
      (node (ref "U301") (pin "P9") (pinfunction "GND_P9") (pintype "power_in"))
      (node (ref "U301") (pin "R10") (pinfunction "GND_R10") (pintype "power_in"))
      (node (ref "U301") (pin "R12") (pinfunction "GND_R12") (pintype "power_in"))
      (node (ref "U301") (pin "R20") (pinfunction "GND_R20") (pintype "power_in"))
      (node (ref "U301") (pin "R8") (pinfunction "GND_R8") (pintype "power_in"))
      (node (ref "U301") (pin "T11") (pinfunction "GND_T11") (pintype "power_in"))
      (node (ref "U301") (pin "T17") (pinfunction "GND_T17") (pintype "power_in"))
      (node (ref "U301") (pin "T7") (pinfunction "GND_T7") (pintype "power_in"))
      (node (ref "U301") (pin "T9") (pinfunction "GND_T9") (pintype "power_in"))
      (node (ref "U301") (pin "U14") (pinfunction "GND_U14") (pintype "power_in"))
      (node (ref "U301") (pin "U4") (pinfunction "GND_U4") (pintype "power_in"))
      (node (ref "U301") (pin "V1") (pinfunction "GND_V1") (pintype "power_in"))
      (node (ref "U301") (pin "V11") (pinfunction "GND_V11") (pintype "power_in"))
      (node (ref "U301") (pin "V21") (pinfunction "GND_V21") (pintype "power_in"))
      (node (ref "U301") (pin "W18") (pinfunction "GND_W18") (pintype "power_in"))
      (node (ref "U301") (pin "W8") (pinfunction "GND_W8") (pintype "power_in"))
      (node (ref "U301") (pin "Y15") (pinfunction "GND_Y15") (pintype "power_in"))
      (node (ref "U301") (pin "Y5") (pinfunction "GND_Y5") (pintype "power_in"))
    )
    (net (code "8") (name "Net-(C302-Pad1)") (class "Default")
      (node (ref "C302") (pin "1") (pinfunction "1_1") (pintype "passive"))
      (node (ref "C303") (pin "1") (pinfunction "1_1") (pintype "passive"))
      (node (ref "C304") (pin "1") (pinfunction "1_1") (pintype "passive"))
      (node (ref "FB301") (pin "2") (pinfunction "2_2") (pintype "passive"))
      (node (ref "U301") (pin "D10") (pinfunction "MGTAVCC_D10") (pintype "power_in"))
      (node (ref "U301") (pin "D6") (pinfunction "MGTAVCC_D6") (pintype "power_in"))
      (node (ref "U301") (pin "E8") (pinfunction "MGTAVCC_E8") (pintype "power_in"))
      (node (ref "U301") (pin "F7") (pinfunction "MGTAVCC_F7") (pintype "power_in"))
      (node (ref "U301") (pin "F9") (pinfunction "MGTAVCC_F9") (pintype "power_in"))
    )
    (net (code "9") (name "Net-(U301J-VCCADC_0)") (class "Default")
      (node (ref "C331") (pin "1") (pinfunction "1_1") (pintype "passive"))
      (node (ref "C332") (pin "1") (pinfunction "1_1") (pintype "passive"))
      (node (ref "FB303") (pin "2") (pinfunction "2_2") (pintype "passive"))
      (node (ref "U301") (pin "K10") (pinfunction "VCCADC_0_K10") (pintype "power_in"))
    )
  )
)
